# esquema_eletrico_eagle.net
KiCad netlist of a schematic drawn in EAGLE
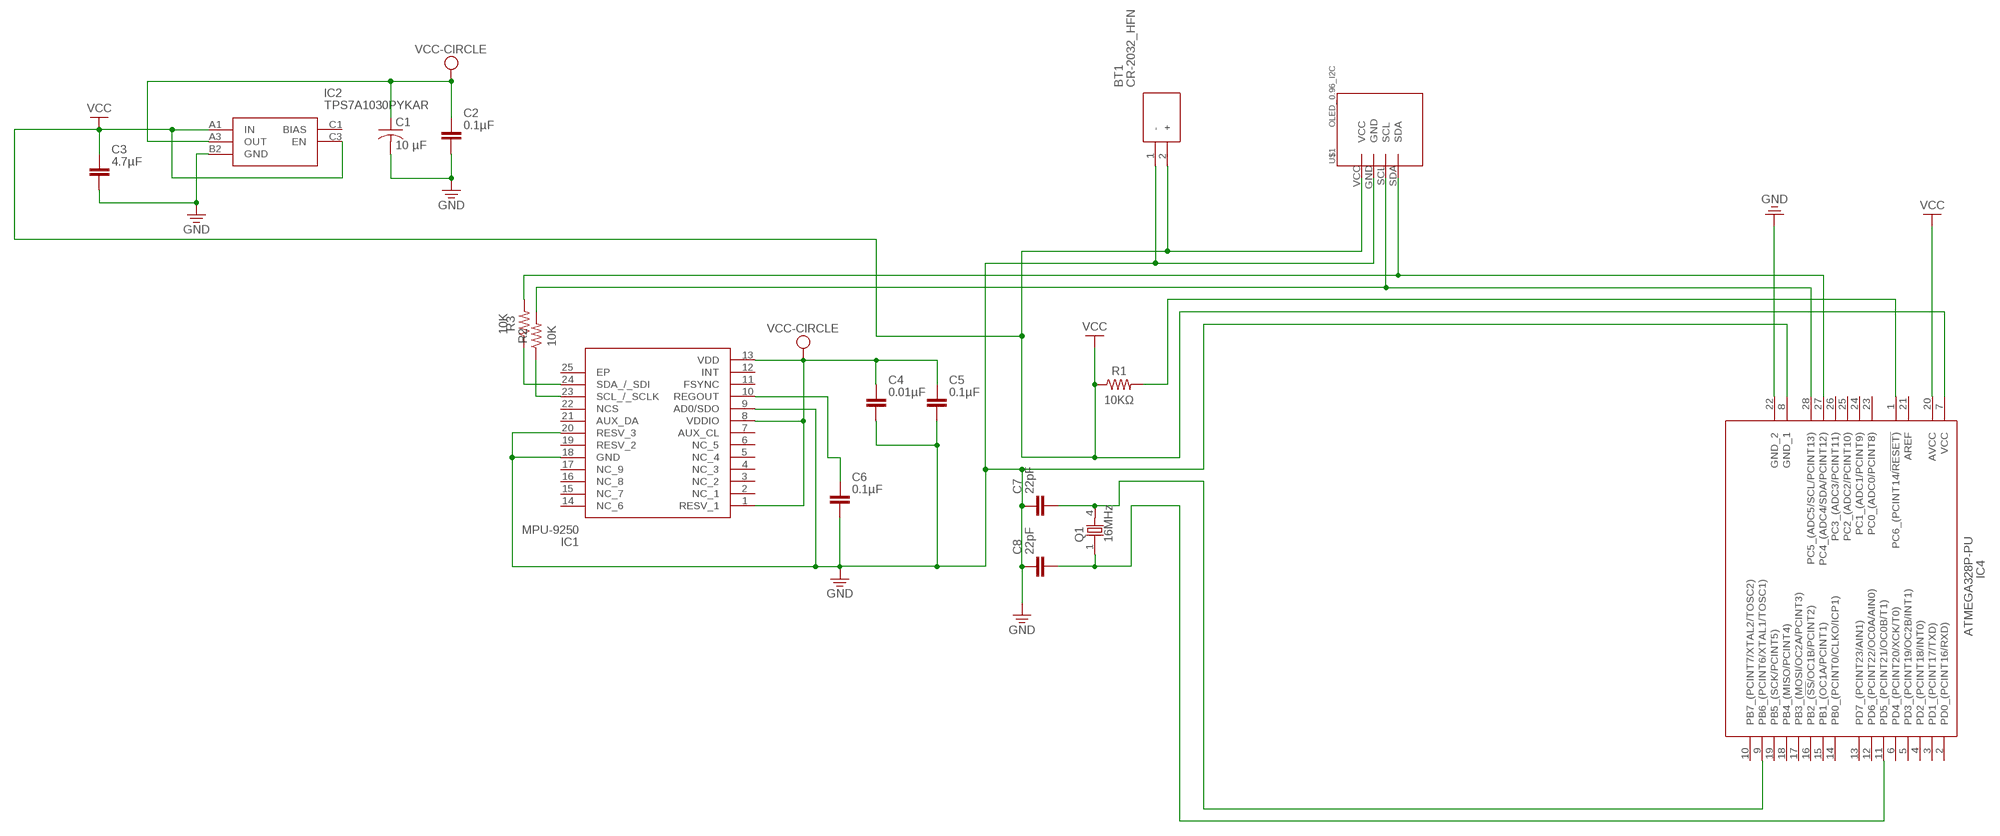
[diagram p0: schematic, sheet 1]

(export (version "E")
  (design (tool "Eeschema 10.0.6"))
  (components
    (comp (ref "BT1")
      (value "CR-2032_HFN")
      (footprint "eagle-import:CR-2032HFN")
      (fields
        (field (name "ARROW_PART_NUMBER") "CR-2032/HFN")
        (field (name "MOUSER_PART_NUMBER") "658-CR-2032/HFN")
      )
      (libsource (lib "eagle-import") (part "CR-2032_HFN"))
    )
    (comp (ref "C1")
      (value "10 µF")
      (footprint "eagle-import:CAPC1005X60")
      (libsource (lib "eagle-import") (part "C-USCHIP-0402(1005-METRIC)_"))
    )
    (comp (ref "C2")
      (value "0.1µF")
      (footprint "eagle-import:CAPC1005X60")
      (libsource (lib "eagle-import") (part "CCHIP-0402(1005-METRIC)_"))
    )
    (comp (ref "C3")
      (value "4.7µF")
      (footprint "eagle-import:CAPC1005X60")
      (libsource (lib "eagle-import") (part "CCHIP-0402(1005-METRIC)_"))
    )
    (comp (ref "C4")
      (value "0.01µF")
      (footprint "eagle-import:CAPC1005X60")
      (libsource (lib "eagle-import") (part "CCHIP-0402(1005-METRIC)_"))
    )
    (comp (ref "C5")
      (value "0.1µF")
      (footprint "eagle-import:CAPC1005X60")
      (libsource (lib "eagle-import") (part "CCHIP-0402(1005-METRIC)_"))
    )
    (comp (ref "C6")
      (value "0.1µF")
      (footprint "eagle-import:CAPC1005X60")
      (libsource (lib "eagle-import") (part "CCHIP-0402(1005-METRIC)_"))
    )
    (comp (ref "C7")
      (value "22pF")
      (footprint "eagle-import:CAPC1005X60")
      (libsource (lib "eagle-import") (part "CCHIP-0402(1005-METRIC)_"))
    )
    (comp (ref "C8")
      (value "22pF")
      (footprint "eagle-import:CAPC1005X60")
      (libsource (lib "eagle-import") (part "CCHIP-0402(1005-METRIC)_"))
    )
    (comp (ref "IC1")
      (value "MPU-9250")
      (footprint "eagle-import:QFN40P300X300X105-25N")
      (fields (field (name "MOUSER_PART_NUMBER") "410-MPU-9250"))
      (libsource (lib "eagle-import") (part "MPU-9250"))
    )
    (comp (ref "IC2")
      (value "TPS7A1030PYKAR")
      (footprint "eagle-import:TPS7A1030PYKAR")
      (fields (field (name "MOUSER_PART_NUMBER") "595-TPS7A1030PYKAR"))
      (libsource (lib "eagle-import") (part "TPS7A1030PYKAR"))
    )
    (comp (ref "IC4")
      (value "ATMEGA328P-PU")
      (footprint "eagle-import:DIP794W53P254L3467H457Q28N")
      (fields (field (name "MOUSER_PART_NUMBER") "556-ATMEGA328P-PU"))
      (libsource (lib "eagle-import") (part "ATMEGA328P-PU"))
    )
    (comp (ref "Q1")
      (value "16MHz")
      (footprint "eagle-import:86SMX")
      (libsource (lib "eagle-import") (part "86SMX"))
    )
    (comp (ref "R1")
      (value "10KΩ")
      (footprint "eagle-import:RESC1608X60")
      (libsource (lib "eagle-import") (part "R-USCHIP-0603(1608-METRIC)_"))
    )
    (comp (ref "R2")
      (value "10K")
      (footprint "eagle-import:RESAD724W46L381D178B")
      (libsource (lib "eagle-import") (part "R-USAXIAL-7.2MM-PITCH_"))
    )
    (comp (ref "R3")
      (value "10K")
      (footprint "eagle-import:RESAD724W46L381D178B")
      (libsource (lib "eagle-import") (part "R-USAXIAL-7.2MM-PITCH_"))
    )
    (comp (ref "U$1")
      (value "OLED_0.96_I2C")
      (footprint "eagle-import:OLED_0.96_I2C")
      (libsource (lib "eagle-import") (part "OLED_0.96_I2C"))
    )
  )
  (nets
    (net (code "1") (name "GND") (class "Default")
      (node (ref "BT1") (pin "1") (pinfunction "-_1") (pintype "bidirectional"))
      (node (ref "C1") (pin "2") (pinfunction "2_2") (pintype "passive"))
      (node (ref "C2") (pin "2") (pinfunction "2_2") (pintype "passive"))
      (node (ref "C3") (pin "2") (pinfunction "2_2") (pintype "passive"))
      (node (ref "C4") (pin "2") (pinfunction "2_2") (pintype "passive"))
      (node (ref "C5") (pin "2") (pinfunction "2_2") (pintype "passive"))
      (node (ref "C6") (pin "2") (pinfunction "2_2") (pintype "passive"))
      (node (ref "C7") (pin "1") (pinfunction "1_1") (pintype "passive"))
      (node (ref "C8") (pin "1") (pinfunction "1_1") (pintype "passive"))
      (node (ref "IC1") (pin "18") (pinfunction "GND_18") (pintype "bidirectional"))
      (node (ref "IC1") (pin "20") (pinfunction "RESV_3_20") (pintype "bidirectional"))
      (node (ref "IC1") (pin "9") (pinfunction "AD0/SDO_9") (pintype "bidirectional"))
      (node (ref "IC2") (pin "B2") (pinfunction "GND_B2") (pintype "bidirectional"))
      (node (ref "IC4") (pin "22") (pinfunction "GND_2_22") (pintype "bidirectional"))
      (node (ref "IC4") (pin "8") (pinfunction "GND_1_8") (pintype "bidirectional"))
      (node (ref "U$1") (pin "GND") (pinfunction "GND_GND") (pintype "bidirectional"))
    )
    (net (code "2") (name "Net-(IC1-REGOUT)") (class "Default")
      (node (ref "C6") (pin "1") (pinfunction "1_1") (pintype "passive"))
      (node (ref "IC1") (pin "10") (pinfunction "REGOUT_10") (pintype "bidirectional"))
    )
    (net (code "3") (name "Net-(IC1-SCL_{slash}_SCLK)") (class "Default")
      (node (ref "IC1") (pin "23") (pinfunction "SCL_/_SCLK_23") (pintype "bidirectional"))
      (node (ref "R2") (pin "1") (pinfunction "1_1") (pintype "passive"))
    )
    (net (code "4") (name "Net-(IC1-SDA_{slash}_SDI)") (class "Default")
      (node (ref "IC1") (pin "24") (pinfunction "SDA_/_SDI_24") (pintype "bidirectional"))
      (node (ref "R3") (pin "1") (pinfunction "1_1") (pintype "passive"))
    )
    (net (code "5") (name "Net-(IC4-PB6_(PCINT6{slash}XTAL1{slash}TOSC1))") (class "Default")
      (node (ref "C7") (pin "2") (pinfunction "2_2") (pintype "passive"))
      (node (ref "IC4") (pin "9") (pinfunction "PB6_(PCINT6/XTAL1/TOSC1)_9") (pintype "bidirectional"))
      (node (ref "Q1") (pin "4") (pinfunction "2_4") (pintype "passive"))
    )
    (net (code "6") (name "Net-(IC4-PC4_(ADC4{slash}SDA{slash}PCINT12))") (class "Default")
      (node (ref "IC4") (pin "27") (pinfunction "PC4_(ADC4/SDA/PCINT12)_27") (pintype "bidirectional"))
      (node (ref "R3") (pin "2") (pinfunction "2_2") (pintype "passive"))
      (node (ref "U$1") (pin "SDA") (pinfunction "SDA_SDA") (pintype "bidirectional"))
    )
    (net (code "7") (name "Net-(IC4-PC5_(ADC5{slash}SCL{slash}PCINT13))") (class "Default")
      (node (ref "IC4") (pin "28") (pinfunction "PC5_(ADC5/SCL/PCINT13)_28") (pintype "bidirectional"))
      (node (ref "R2") (pin "2") (pinfunction "2_2") (pintype "passive"))
      (node (ref "U$1") (pin "SCL") (pinfunction "SCL_SCL") (pintype "bidirectional"))
    )
    (net (code "8") (name "Net-(IC4-PC6_(PCINT14{slash}~{RESET}))") (class "Default")
      (node (ref "IC4") (pin "1") (pinfunction "PC6_(PCINT14/~{RESET})_1") (pintype "bidirectional"))
      (node (ref "R1") (pin "2") (pinfunction "2_2") (pintype "passive"))
    )
    (net (code "9") (name "Net-(IC4-PD5_(PCINT21{slash}OC0B{slash}T1))") (class "Default")
      (node (ref "C8") (pin "2") (pinfunction "2_2") (pintype "passive"))
      (node (ref "IC4") (pin "11") (pinfunction "PD5_(PCINT21/OC0B/T1)_11") (pintype "bidirectional"))
      (node (ref "Q1") (pin "1") (pinfunction "1_1") (pintype "passive"))
    )
    (net (code "10") (name "VCC") (class "Default")
      (node (ref "BT1") (pin "2") (pinfunction "+_2") (pintype "bidirectional"))
      (node (ref "C1") (pin "1") (pinfunction "1_1") (pintype "passive"))
      (node (ref "C2") (pin "1") (pinfunction "1_1") (pintype "passive"))
      (node (ref "C3") (pin "1") (pinfunction "1_1") (pintype "passive"))
      (node (ref "C4") (pin "1") (pinfunction "1_1") (pintype "passive"))
      (node (ref "C5") (pin "1") (pinfunction "1_1") (pintype "passive"))
      (node (ref "IC1") (pin "1") (pinfunction "RESV_1_1") (pintype "bidirectional"))
      (node (ref "IC1") (pin "13") (pinfunction "VDD_13") (pintype "bidirectional"))
      (node (ref "IC1") (pin "8") (pinfunction "VDDIO_8") (pintype "bidirectional"))
      (node (ref "IC2") (pin "A1") (pinfunction "IN_A1") (pintype "bidirectional"))
      (node (ref "IC2") (pin "A3") (pinfunction "OUT_A3") (pintype "bidirectional"))
      (node (ref "IC2") (pin "C3") (pinfunction "EN_C3") (pintype "bidirectional"))
      (node (ref "IC4") (pin "20") (pinfunction "AVCC_20") (pintype "bidirectional"))
      (node (ref "IC4") (pin "7") (pinfunction "VCC_7") (pintype "bidirectional"))
      (node (ref "R1") (pin "1") (pinfunction "1_1") (pintype "passive"))
      (node (ref "U$1") (pin "VCC") (pinfunction "VCC_VCC") (pintype "bidirectional"))
    )
    (net (code "11") (name "unconnected-(IC1-AUX_CL-Pad7)") (class "Default")
      (node (ref "IC1") (pin "7") (pinfunction "AUX_CL_7") (pintype "bidirectional"))
    )
    (net (code "12") (name "unconnected-(IC1-AUX_DA-Pad21)") (class "Default")
      (node (ref "IC1") (pin "21") (pinfunction "AUX_DA_21") (pintype "bidirectional"))
    )
    (net (code "13") (name "unconnected-(IC1-EP-Pad25)") (class "Default")
      (node (ref "IC1") (pin "25") (pinfunction "EP_25") (pintype "bidirectional"))
    )
    (net (code "14") (name "unconnected-(IC1-FSYNC-Pad11)") (class "Default")
      (node (ref "IC1") (pin "11") (pinfunction "FSYNC_11") (pintype "bidirectional"))
    )
    (net (code "15") (name "unconnected-(IC1-INT-Pad12)") (class "Default")
      (node (ref "IC1") (pin "12") (pinfunction "INT_12") (pintype "bidirectional"))
    )
    (net (code "16") (name "unconnected-(IC1-NCS-Pad22)") (class "Default")
      (node (ref "IC1") (pin "22") (pinfunction "NCS_22") (pintype "bidirectional"))
    )
    (net (code "17") (name "unconnected-(IC1-NC_1-Pad2)") (class "Default")
      (node (ref "IC1") (pin "2") (pinfunction "NC_1_2") (pintype "bidirectional"))
    )
    (net (code "18") (name "unconnected-(IC1-NC_2-Pad3)") (class "Default")
      (node (ref "IC1") (pin "3") (pinfunction "NC_2_3") (pintype "bidirectional"))
    )
    (net (code "19") (name "unconnected-(IC1-NC_3-Pad4)") (class "Default")
      (node (ref "IC1") (pin "4") (pinfunction "NC_3_4") (pintype "bidirectional"))
    )
    (net (code "20") (name "unconnected-(IC1-NC_4-Pad5)") (class "Default")
      (node (ref "IC1") (pin "5") (pinfunction "NC_4_5") (pintype "bidirectional"))
    )
    (net (code "21") (name "unconnected-(IC1-NC_5-Pad6)") (class "Default")
      (node (ref "IC1") (pin "6") (pinfunction "NC_5_6") (pintype "bidirectional"))
    )
    (net (code "22") (name "unconnected-(IC1-NC_6-Pad14)") (class "Default")
      (node (ref "IC1") (pin "14") (pinfunction "NC_6_14") (pintype "bidirectional"))
    )
    (net (code "23") (name "unconnected-(IC1-NC_7-Pad15)") (class "Default")
      (node (ref "IC1") (pin "15") (pinfunction "NC_7_15") (pintype "bidirectional"))
    )
    (net (code "24") (name "unconnected-(IC1-NC_8-Pad16)") (class "Default")
      (node (ref "IC1") (pin "16") (pinfunction "NC_8_16") (pintype "bidirectional"))
    )
    (net (code "25") (name "unconnected-(IC1-NC_9-Pad17)") (class "Default")
      (node (ref "IC1") (pin "17") (pinfunction "NC_9_17") (pintype "bidirectional"))
    )
    (net (code "26") (name "unconnected-(IC1-RESV_2-Pad19)") (class "Default")
      (node (ref "IC1") (pin "19") (pinfunction "RESV_2_19") (pintype "bidirectional"))
    )
    (net (code "27") (name "unconnected-(IC2-BIAS-PadC1)") (class "Default")
      (node (ref "IC2") (pin "C1") (pinfunction "BIAS_C1") (pintype "bidirectional"))
    )
    (net (code "28") (name "unconnected-(IC4-AREF-Pad21)") (class "Default")
      (node (ref "IC4") (pin "21") (pinfunction "AREF_21") (pintype "bidirectional"))
    )
    (net (code "29") (name "unconnected-(IC4-PB0_(PCINT0{slash}CLKO{slash}ICP1)-Pad14)") (class "Default")
      (node (ref "IC4") (pin "14") (pinfunction "PB0_(PCINT0/CLKO/ICP1)_14") (pintype "bidirectional"))
    )
    (net (code "30") (name "unconnected-(IC4-PB1_(OC1A{slash}PCINT1)-Pad15)") (class "Default")
      (node (ref "IC4") (pin "15") (pinfunction "PB1_(OC1A/PCINT1)_15") (pintype "bidirectional"))
    )
    (net (code "31") (name "unconnected-(IC4-PB2_(~{SS}{slash}OC1B{slash}PCINT2)-Pad16)") (class "Default")
      (node (ref "IC4") (pin "16") (pinfunction "PB2_(~{SS}/OC1B/PCINT2)_16") (pintype "bidirectional"))
    )
    (net (code "32") (name "unconnected-(IC4-PB3_(MOSI{slash}OC2A{slash}PCINT3)-Pad17)") (class "Default")
      (node (ref "IC4") (pin "17") (pinfunction "PB3_(MOSI/OC2A/PCINT3)_17") (pintype "bidirectional"))
    )
    (net (code "33") (name "unconnected-(IC4-PB4_(MISO{slash}PCINT4)-Pad18)") (class "Default")
      (node (ref "IC4") (pin "18") (pinfunction "PB4_(MISO/PCINT4)_18") (pintype "bidirectional"))
    )
    (net (code "34") (name "unconnected-(IC4-PB5_(SCK{slash}PCINT5)-Pad19)") (class "Default")
      (node (ref "IC4") (pin "19") (pinfunction "PB5_(SCK/PCINT5)_19") (pintype "bidirectional"))
    )
    (net (code "35") (name "unconnected-(IC4-PB7_(PCINT7{slash}XTAL2{slash}TOSC2)-Pad10)") (class "Default")
      (node (ref "IC4") (pin "10") (pinfunction "PB7_(PCINT7/XTAL2/TOSC2)_10") (pintype "bidirectional"))
    )
    (net (code "36") (name "unconnected-(IC4-PC0_(ADC0{slash}PCINT8)-Pad23)") (class "Default")
      (node (ref "IC4") (pin "23") (pinfunction "PC0_(ADC0/PCINT8)_23") (pintype "bidirectional"))
    )
    (net (code "37") (name "unconnected-(IC4-PC1_(ADC1{slash}PCINT9)-Pad24)") (class "Default")
      (node (ref "IC4") (pin "24") (pinfunction "PC1_(ADC1/PCINT9)_24") (pintype "bidirectional"))
    )
    (net (code "38") (name "unconnected-(IC4-PC2_(ADC2{slash}PCINT10)-Pad25)") (class "Default")
      (node (ref "IC4") (pin "25") (pinfunction "PC2_(ADC2/PCINT10)_25") (pintype "bidirectional"))
    )
    (net (code "39") (name "unconnected-(IC4-PC3_(ADC3{slash}PCINT11)-Pad26)") (class "Default")
      (node (ref "IC4") (pin "26") (pinfunction "PC3_(ADC3/PCINT11)_26") (pintype "bidirectional"))
    )
    (net (code "40") (name "unconnected-(IC4-PD0_(PCINT16{slash}RXD)-Pad2)") (class "Default")
      (node (ref "IC4") (pin "2") (pinfunction "PD0_(PCINT16/RXD)_2") (pintype "bidirectional"))
    )
    (net (code "41") (name "unconnected-(IC4-PD1_(PCINT17{slash}TXD)-Pad3)") (class "Default")
      (node (ref "IC4") (pin "3") (pinfunction "PD1_(PCINT17/TXD)_3") (pintype "bidirectional"))
    )
    (net (code "42") (name "unconnected-(IC4-PD2_(PCINT18{slash}INT0)-Pad4)") (class "Default")
      (node (ref "IC4") (pin "4") (pinfunction "PD2_(PCINT18/INT0)_4") (pintype "bidirectional"))
    )
    (net (code "43") (name "unconnected-(IC4-PD3_(PCINT19{slash}OC2B{slash}INT1)-Pad5)") (class "Default")
      (node (ref "IC4") (pin "5") (pinfunction "PD3_(PCINT19/OC2B/INT1)_5") (pintype "bidirectional"))
    )
    (net (code "44") (name "unconnected-(IC4-PD4_(PCINT20{slash}XCK{slash}T0)-Pad6)") (class "Default")
      (node (ref "IC4") (pin "6") (pinfunction "PD4_(PCINT20/XCK/T0)_6") (pintype "bidirectional"))
    )
    (net (code "45") (name "unconnected-(IC4-PD6_(PCINT22{slash}OC0A{slash}AIN0)-Pad12)") (class "Default")
      (node (ref "IC4") (pin "12") (pinfunction "PD6_(PCINT22/OC0A/AIN0)_12") (pintype "bidirectional"))
    )
    (net (code "46") (name "unconnected-(IC4-PD7_(PCINT23{slash}AIN1)-Pad13)") (class "Default")
      (node (ref "IC4") (pin "13") (pinfunction "PD7_(PCINT23/AIN1)_13") (pintype "bidirectional"))
    )
  )
)
